# LDO_USB.net
KiCad netlist of a schematic drawn in Altium Designer
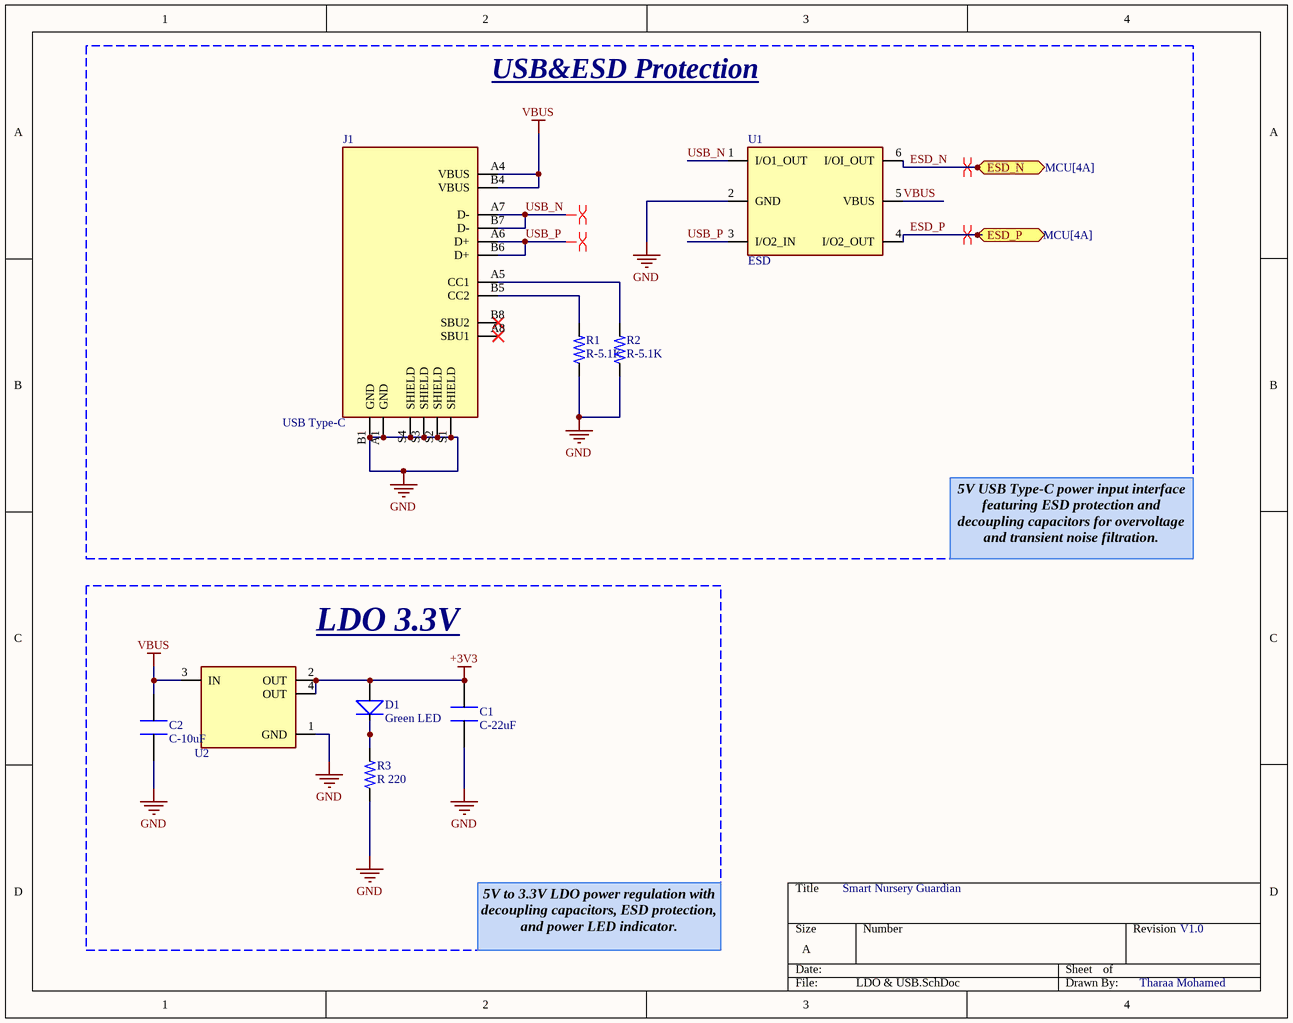
[diagram p0: LDO & USB.SchDoc]

(export (version "E")
  (design (tool "Eeschema 10.0.6"))
  (components
    (comp (ref "C1")
      (value "C-22uF")
      (footprint "C-22uF")
      (fields (field (name "MFR") "muRata") (field (name "MJFR PART #") "GRM21BR61E226ME44L"))
      (libsource (lib "Schlib1") (part "C-22uF"))
    )
    (comp (ref "C2")
      (value "C-10uF")
      (footprint "C-10uF")
      (fields (field (name "MFR") "Samsung Electro-Mechanics") (field (name "MFR PART #") "CL31A106KBHNNNE"))
      (libsource (lib "Schlib1") (part "C-10uF"))
    )
    (comp (ref "D1")
      (value "Green LED")
      (footprint "Green LED")
      (fields (field (name "MFR") "NATIONSTAR"))
      (libsource (lib "Schlib1") (part "Green LED"))
    )
    (comp (ref "J1")
      (value "USB Type-C")
      (footprint "USB_Type-C")
      (fields (field (name "MFR") "Korean Hroparts Elec") (field (name "MFR PART #") "TYPE-C-31-M-12"))
      (libsource (lib "Schlib1") (part "USB Type-C"))
    )
    (comp (ref "R1")
      (value "R-5.1K")
      (footprint "R-5.1K")
      (fields (field (name "MFR") "YAGEO") (field (name "MFR PART #") "RC0402FR-075K1L"))
      (libsource (lib "Schlib1") (part "R-5.1K"))
    )
    (comp (ref "R2")
      (value "R-5.1K")
      (footprint "R-5.1K")
      (fields (field (name "MFR") "YAGEO") (field (name "MFR PART #") "RC0402FR-075K1L"))
      (libsource (lib "Schlib1") (part "R-5.1K"))
    )
    (comp (ref "R3")
      (value "R 220")
      (footprint "R-220")
      (fields (field (name "MFR") "UNI-ROYAL") (field (name "MFR PART #") "0603WAF2200T5E"))
      (libsource (lib "Schlib1") (part "R 220"))
    )
    (comp (ref "U1")
      (value "ESD")
      (footprint "ESD")
      (fields (field (name "MFR") "ST") (field (name "MFR PART #") "USBLC6-2SC6"))
      (libsource (lib "Schlib1") (part "ESD"))
    )
    (comp (ref "U2")
      (value "LDO 3.3")
      (footprint "LDO 3.3")
      (fields
        (field (name "MFR") "Advanced Monolithic Systems")
        (field (name "MFR PART #") "LTC1844ES5-3.3#TRMPBF")
        (field (name "MFR PART") "AMS1117-3.3")
      )
      (libsource (lib "Schlib1") (part "LDO 3.3"))
    )
  )
  (nets
    (net (code "1") (name "+3V3") (class "Default")
      (node (ref "C1") (pin "2") (pinfunction "2_2") (pintype "passive"))
      (node (ref "D1") (pin "2") (pinfunction "2_2") (pintype "passive"))
      (node (ref "U2") (pin "2") (pinfunction "OUT_2") (pintype "passive"))
      (node (ref "U2") (pin "4") (pinfunction "OUT_4") (pintype "passive"))
    )
    (net (code "2") (name "/ESD_N") (class "Default")
      (node (ref "U1") (pin "6") (pinfunction "I/OI_OUT_6") (pintype "passive"))
    )
    (net (code "3") (name "/ESD_P") (class "Default")
      (node (ref "U1") (pin "4") (pinfunction "I/O2_OUT_4") (pintype "passive"))
    )
    (net (code "4") (name "/USB_N") (class "Default")
      (node (ref "J1") (pin "A7") (pinfunction "D-_A7") (pintype "passive"))
      (node (ref "J1") (pin "B7") (pinfunction "D-_B7") (pintype "passive"))
      (node (ref "U1") (pin "1") (pinfunction "I/O1_OUT_1") (pintype "passive"))
    )
    (net (code "5") (name "/USB_P") (class "Default")
      (node (ref "J1") (pin "A6") (pinfunction "D+_A6") (pintype "passive"))
      (node (ref "J1") (pin "B6") (pinfunction "D+_B6") (pintype "passive"))
      (node (ref "U1") (pin "3") (pinfunction "I/O2_IN_3") (pintype "passive"))
    )
    (net (code "6") (name "GND") (class "Default")
      (node (ref "C1") (pin "1") (pinfunction "1_1") (pintype "passive"))
      (node (ref "C2") (pin "1") (pinfunction "1_1") (pintype "passive"))
      (node (ref "J1") (pin "A1") (pinfunction "GND_A1") (pintype "passive"))
      (node (ref "J1") (pin "B1") (pinfunction "GND_B1") (pintype "passive"))
      (node (ref "J1") (pin "S1") (pinfunction "SHIELD_S1") (pintype "passive"))
      (node (ref "J1") (pin "S2") (pinfunction "SHIELD_S2") (pintype "passive"))
      (node (ref "J1") (pin "S3") (pinfunction "SHIELD_S3") (pintype "passive"))
      (node (ref "J1") (pin "S4") (pinfunction "SHIELD_S4") (pintype "passive"))
      (node (ref "R1") (pin "1") (pinfunction "1_1") (pintype "passive"))
      (node (ref "R2") (pin "1") (pinfunction "1_1") (pintype "passive"))
      (node (ref "R3") (pin "1") (pinfunction "1_1") (pintype "passive"))
      (node (ref "U1") (pin "2") (pinfunction "GND_2") (pintype "passive"))
      (node (ref "U2") (pin "1") (pinfunction "GND_1") (pintype "passive"))
    )
    (net (code "7") (name "Net-(D1-Pad1)") (class "Default")
      (node (ref "D1") (pin "1") (pinfunction "1_1") (pintype "passive"))
      (node (ref "R3") (pin "2") (pinfunction "2_2") (pintype "passive"))
    )
    (net (code "8") (name "Net-(J1-CC1)") (class "Default")
      (node (ref "J1") (pin "A5") (pinfunction "CC1_A5") (pintype "passive"))
      (node (ref "R2") (pin "2") (pinfunction "2_2") (pintype "passive"))
    )
    (net (code "9") (name "Net-(J1-CC2)") (class "Default")
      (node (ref "J1") (pin "B5") (pinfunction "CC2_B5") (pintype "passive"))
      (node (ref "R1") (pin "2") (pinfunction "2_2") (pintype "passive"))
    )
    (net (code "10") (name "VBUS") (class "Default")
      (node (ref "C2") (pin "2") (pinfunction "2_2") (pintype "passive"))
      (node (ref "J1") (pin "A4") (pinfunction "VBUS_A4") (pintype "passive"))
      (node (ref "J1") (pin "B4") (pinfunction "VBUS_B4") (pintype "passive"))
      (node (ref "U1") (pin "5") (pinfunction "VBUS_5") (pintype "passive"))
      (node (ref "U2") (pin "3") (pinfunction "IN_3") (pintype "passive"))
    )
    (net (code "11") (name "unconnected-(J1-SBU1-PadA8)") (class "Default")
      (node (ref "J1") (pin "A8") (pinfunction "SBU1_A8") (pintype "passive+no_connect"))
    )
    (net (code "12") (name "unconnected-(J1-SBU2-PadB8)") (class "Default")
      (node (ref "J1") (pin "B8") (pinfunction "SBU2_B8") (pintype "passive+no_connect"))
    )
  )
)
